# Power.net
KiCad netlist of a schematic drawn in Altium Designer
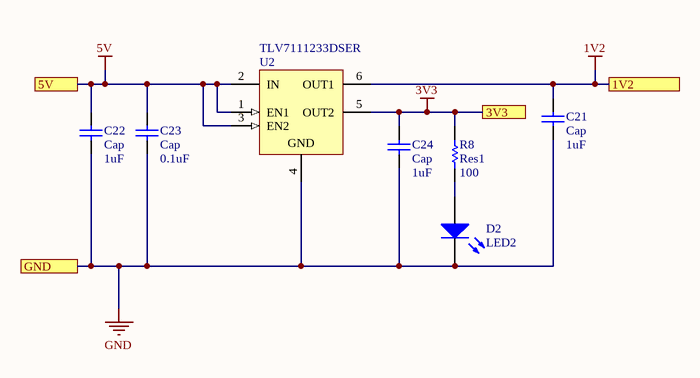
[diagram p0: Power.SchDoc]

(export (version "E")
  (design (tool "Eeschema 10.0.6"))
  (components
    (comp (ref "C21")
      (value "Cap")
      (footprint "RAD-0.3")
      (description "Capacitor")
      (fields (field (name "ALTIUM_VALUE") "1uF") (field (name "PUBLISHER") "Altium Limited"))
      (libsource (lib "Miscellaneous Devices") (part "Cap"))
    )
    (comp (ref "C22")
      (value "Cap")
      (footprint "RAD-0.3")
      (description "Capacitor")
      (fields (field (name "ALTIUM_VALUE") "1uF") (field (name "PUBLISHER") "Altium Limited"))
      (libsource (lib "Miscellaneous Devices") (part "Cap"))
    )
    (comp (ref "C23")
      (value "Cap")
      (footprint "RAD-0.3")
      (description "Capacitor")
      (fields (field (name "ALTIUM_VALUE") "0.1uF") (field (name "PUBLISHER") "Altium Limited"))
      (libsource (lib "Miscellaneous Devices") (part "Cap"))
    )
    (comp (ref "C24")
      (value "Cap")
      (footprint "RAD-0.3")
      (description "Capacitor")
      (fields (field (name "ALTIUM_VALUE") "1uF") (field (name "PUBLISHER") "Altium Limited"))
      (libsource (lib "Miscellaneous Devices") (part "Cap"))
    )
    (comp (ref "D2")
      (value "LED2")
      (footprint "3.2X1.6X1.1")
      (description "Typical RED, GREEN, YELLOW, AMBER GaAs LED")
      (fields (field (name "PUBLISHER") "Altium Limited"))
      (libsource (lib "Miscellaneous Devices") (part "LED2"))
    )
    (comp (ref "R8")
      (value "Res1")
      (footprint "AXIAL-0.3")
      (description "Resistor")
      (fields (field (name "ALTIUM_VALUE") "100") (field (name "PUBLISHER") "Altium Limited"))
      (libsource (lib "Miscellaneous Devices") (part "Res1"))
    )
    (comp (ref "U2")
      (value "TLV7111233DSER")
      (footprint "TI-DSE6_V")
      (fields (field (name "MANUFACTURER") "Texas Instruments"))
      (libsource (lib "TI Power Management Linear Regulator Dual Channel LDO") (part "TLV7111233DSER"))
    )
  )
  (nets
    (net (code "1") (name "1V2") (class "Default")
      (node (ref "C21") (pin "2") (pinfunction "2_2") (pintype "passive"))
      (node (ref "U2") (pin "6") (pinfunction "OUT1_6") (pintype "power_in"))
    )
    (net (code "2") (name "3V3") (class "Default")
      (node (ref "C24") (pin "2") (pinfunction "2_2") (pintype "passive"))
      (node (ref "R8") (pin "2") (pinfunction "2_2") (pintype "passive"))
      (node (ref "U2") (pin "5") (pinfunction "OUT2_5") (pintype "power_in"))
    )
    (net (code "3") (name "5V") (class "Default")
      (node (ref "C22") (pin "1") (pinfunction "1_1") (pintype "passive"))
      (node (ref "C23") (pin "2") (pinfunction "2_2") (pintype "passive"))
      (node (ref "U2") (pin "1") (pinfunction "EN1_1") (pintype "input"))
      (node (ref "U2") (pin "2") (pinfunction "IN_2") (pintype "power_in"))
      (node (ref "U2") (pin "3") (pinfunction "EN2_3") (pintype "input"))
    )
    (net (code "4") (name "GND") (class "Default")
      (node (ref "C21") (pin "1") (pinfunction "1_1") (pintype "passive"))
      (node (ref "C22") (pin "2") (pinfunction "2_2") (pintype "passive"))
      (node (ref "C23") (pin "1") (pinfunction "1_1") (pintype "passive"))
      (node (ref "C24") (pin "1") (pinfunction "1_1") (pintype "passive"))
      (node (ref "D2") (pin "2") (pinfunction "K_2") (pintype "passive"))
      (node (ref "U2") (pin "4") (pinfunction "GND_4") (pintype "power_in"))
    )
    (net (code "5") (name "Net-(D2-A)") (class "Default")
      (node (ref "D2") (pin "1") (pinfunction "A_1") (pintype "passive"))
      (node (ref "R8") (pin "1") (pinfunction "1_1") (pintype "passive"))
    )
  )
)
